# MCU.net
KiCad netlist of a schematic drawn in Altium Designer
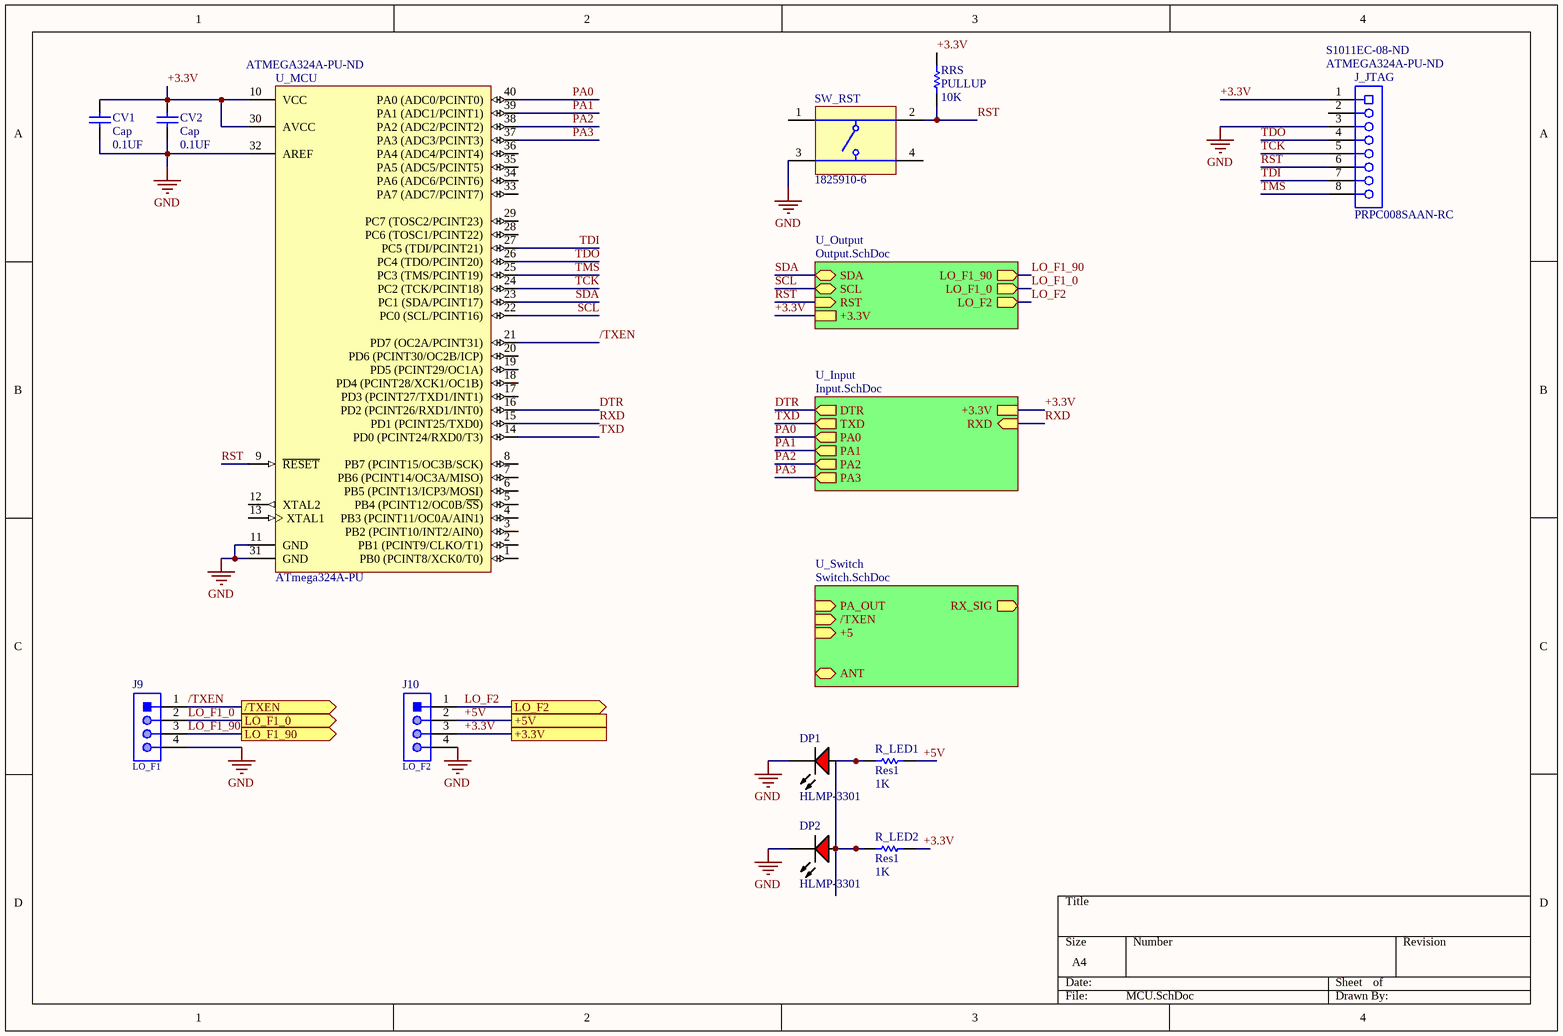
[diagram p0: MCU.SchDoc]

(export (version "E")
  (design (tool "Eeschema 10.0.6"))
  (components
    (comp (ref "CV1")
      (value "Cap")
      (footprint "1206")
      (description "Capacitor")
      (fields
        (field (name "ALTIUM_VALUE") "0.1UF")
        (field (name "MANUFACTURER PART NUMBER") "885012208087")
        (field (name "PUBLISHER") "Altium Limited")
      )
      (libsource (lib "ECE295-Capacitors-SMT") (part "CAP CER 0.1UF 50V X7R 1206"))
    )
    (comp (ref "CV2")
      (value "Cap")
      (footprint "1206")
      (description "Capacitor")
      (fields
        (field (name "ALTIUM_VALUE") "0.1UF")
        (field (name "MANUFACTURER PART NUMBER") "885012208087")
        (field (name "PUBLISHER") "Altium Limited")
      )
      (libsource (lib "ECE295-Capacitors-SMT") (part "CAP CER 0.1UF 50V X7R 1206"))
    )
    (comp (ref "DP1")
      (value "HLMP-3301")
      (footprint "AVAG-HLMP-3301-2")
      (description "T-1 3/4 (5 mm) Diffused LED Lamp, 1.9 V, -40 to 100 degC, 2-Pin THD, RoHS, Bulk")
      (fields (field (name "MANUFACTURER") "Avago"))
      (libsource (lib "Altium Content Vault") (part "LED-RED-K1A2-2"))
    )
    (comp (ref "DP2")
      (value "HLMP-3301")
      (footprint "AVAG-HLMP-3301-2")
      (description "T-1 3/4 (5 mm) Diffused LED Lamp, 1.9 V, -40 to 100 degC, 2-Pin THD, RoHS, Bulk")
      (fields (field (name "MANUFACTURER") "Avago"))
      (libsource (lib "Altium Content Vault") (part "LED-RED-K1A2-2"))
    )
    (comp (ref "J9")
      (value "LO_F1")
      (footprint "61300411121")
      (description "THT Vertical Pin Header WR-PHD, Pitch 2.54 mm, Single Row, 4 pins")
      (fields
        (field (name "MANUFACTURER") "Wurth Elektronik")
        (field (name "PART NUMBER") "61300411121")
        (field (name "PUBLISHER") "WurthElektronik")
      )
      (libsource (lib "Altium Content Vault") (part "WE-CN-1P-M-R4"))
    )
    (comp (ref "J10")
      (value "LO_F2")
      (footprint "61300411121")
      (description "THT Vertical Pin Header WR-PHD, Pitch 2.54 mm, Single Row, 4 pins")
      (fields
        (field (name "MANUFACTURER") "Wurth Elektronik")
        (field (name "PART NUMBER") "61300411121")
        (field (name "PUBLISHER") "WurthElektronik")
      )
      (libsource (lib "Altium Content Vault") (part "WE-CN-1P-M-R4"))
    )
    (comp (ref "J_JTAG")
      (value "PRPC008SAAN-RC")
      (footprint "SLIN-PPPC081LFBN-RC_V")
      (fields
        (field (name "SUPPLIER PART NUMBER 1") "ATMEGA324A-PU-ND")
        (field (name "MANUFACTURER") "Microchip")
        (field (name "MANUFACTURER PART NUMBER") "ATMEGA324A-PU")
        (field (name "SUPPLIER PART NUMBER 2") "S1011EC-08-ND")
      )
      (libsource (lib "Altium Content Vault") (part "CN-1P-F-R8"))
    )
    (comp (ref "RRS")
      (value "PULLUP")
      (footprint "AXIAL-0.1-RES")
      (description "Resistor")
      (fields
        (field (name "ALTIUM_VALUE") "10K")
        (field (name "MANUFACTURER PART NUMBER") "CFR-25JB-52-10K")
        (field (name "TOLERANCE") "0.05")
        (field (name "PUBLISHER") "Altium Limited")
      )
      (libsource (lib "ECE295-Resistors-TH") (part "RES 10K OHM 5% 1/4W AXIAL"))
    )
    (comp (ref "R_LED1")
      (value "Res1")
      (footprint "AXIAL-0.1-RES")
      (description "Resistor")
      (fields
        (field (name "MANUFACTURER PART NUMBER") "CFR-25JB-52-1K")
        (field (name "TOLERANCE") "0.05")
        (field (name "ALTIUM_VALUE") "1K")
        (field (name "PUBLISHER") "Altium Limited")
      )
      (libsource (lib "ECE295-Resistors-TH") (part "RES 1K OHM 5% 1/4W AXIAL"))
    )
    (comp (ref "R_LED2")
      (value "Res1")
      (footprint "AXIAL-0.1-RES")
      (description "Resistor")
      (fields
        (field (name "MANUFACTURER PART NUMBER") "CFR-25JB-52-1K")
        (field (name "TOLERANCE") "0.05")
        (field (name "ALTIUM_VALUE") "1K")
        (field (name "PUBLISHER") "Altium Limited")
      )
      (libsource (lib "ECE295-Resistors-TH") (part "RES 1K OHM 5% 1/4W AXIAL"))
    )
    (comp (ref "SW_RST")
      (value "1825910-6")
      (footprint "TECO-1825910-6_V")
      (description "Tact Switch, SPST-NO, 0.05 A, -35 to 85 degC, 4-Pin THD, RoHS, Bulk")
      (fields (field (name "MANUFACTURER") "TE Connectivity"))
      (libsource (lib "Altium Content Vault") (part "SW-SPST-4_A"))
    )
    (comp (ref "U_MCU")
      (value "ATmega324A-PU")
      (footprint "40P6")
      (fields
        (field (name "SUPPLIER PART NUMBER 1") "ATMEGA324A-PU-ND")
        (field (name "MANUFACTURER") "Microchip")
        (field (name "MANUFACTURER PART NUMBER") "ATMEGA324A-PU")
      )
      (libsource (lib "Altium Content Vault") (part "MC-8B-ATM128-IL40"))
    )
  )
  (nets
    (net (code "1") (name "/+3.3V") (class "Default")
      (node (ref "CV1") (pin "2") (pinfunction "2_2") (pintype "passive"))
      (node (ref "CV2") (pin "2") (pinfunction "2_2") (pintype "passive"))
      (node (ref "J10") (pin "3") (pinfunction "3_3") (pintype "passive"))
      (node (ref "J_JTAG") (pin "1") (pinfunction "1_1") (pintype "passive"))
      (node (ref "RRS") (pin "2") (pinfunction "2_2") (pintype "passive"))
      (node (ref "R_LED2") (pin "2") (pinfunction "2_2") (pintype "passive"))
      (node (ref "U_MCU") (pin "10") (pinfunction "VCC_10") (pintype "power_in"))
      (node (ref "U_MCU") (pin "30") (pinfunction "AVCC_30") (pintype "power_in"))
    )
    (net (code "3") (name "/+5V") (class "Default")
      (node (ref "J10") (pin "2") (pinfunction "2_2") (pintype "passive"))
      (node (ref "R_LED1") (pin "2") (pinfunction "2_2") (pintype "passive"))
    )
    (net (code "5") (name "/DTR") (class "Default")
      (node (ref "U_MCU") (pin "16") (pinfunction "PD2_(PCINT26/RXD1/INT0)_16") (pintype "bidirectional"))
    )
    (net (code "6") (name "/LO_F1_0") (class "Default")
      (node (ref "J9") (pin "2") (pinfunction "2_2") (pintype "passive"))
    )
    (net (code "7") (name "/LO_F1_90") (class "Default")
      (node (ref "J9") (pin "3") (pinfunction "3_3") (pintype "passive"))
    )
    (net (code "8") (name "/LO_F2") (class "Default")
      (node (ref "J10") (pin "1") (pinfunction "1_1") (pintype "passive"))
    )
    (net (code "9") (name "/PA0") (class "Default")
      (node (ref "U_MCU") (pin "40") (pinfunction "PA0_(ADC0/PCINT0)_40") (pintype "bidirectional"))
    )
    (net (code "10") (name "/PA1") (class "Default")
      (node (ref "U_MCU") (pin "39") (pinfunction "PA1_(ADC1/PCINT1)_39") (pintype "bidirectional"))
    )
    (net (code "11") (name "/PA2") (class "Default")
      (node (ref "U_MCU") (pin "38") (pinfunction "PA2_(ADC2/PCINT2)_38") (pintype "bidirectional"))
    )
    (net (code "12") (name "/PA3") (class "Default")
      (node (ref "U_MCU") (pin "37") (pinfunction "PA3_(ADC3/PCINT3)_37") (pintype "bidirectional"))
    )
    (net (code "14") (name "/RST") (class "Default")
      (node (ref "J_JTAG") (pin "6") (pinfunction "6_6") (pintype "passive"))
      (node (ref "RRS") (pin "1") (pinfunction "1_1") (pintype "passive"))
      (node (ref "SW_RST") (pin "2") (pinfunction "2_2") (pintype "passive"))
      (node (ref "U_MCU") (pin "9") (pinfunction "~{RESET}_9") (pintype "input"))
    )
    (net (code "15") (name "/RXD") (class "Default")
      (node (ref "U_MCU") (pin "15") (pinfunction "PD1_(PCINT25/TXD0)_15") (pintype "bidirectional"))
    )
    (net (code "17") (name "/SCL") (class "Default")
      (node (ref "U_MCU") (pin "22") (pinfunction "PC0_(SCL/PCINT16)_22") (pintype "bidirectional"))
    )
    (net (code "18") (name "/SDA") (class "Default")
      (node (ref "U_MCU") (pin "23") (pinfunction "PC1_(SDA/PCINT17)_23") (pintype "bidirectional"))
    )
    (net (code "19") (name "/TCK") (class "Default")
      (node (ref "J_JTAG") (pin "5") (pinfunction "5_5") (pintype "passive"))
      (node (ref "U_MCU") (pin "24") (pinfunction "PC2_(TCK/PCINT18)_24") (pintype "bidirectional"))
    )
    (net (code "20") (name "/TDI") (class "Default")
      (node (ref "J_JTAG") (pin "7") (pinfunction "7_7") (pintype "passive"))
      (node (ref "U_MCU") (pin "27") (pinfunction "PC5_(TDI/PCINT21)_27") (pintype "bidirectional"))
    )
    (net (code "21") (name "/TDO") (class "Default")
      (node (ref "J_JTAG") (pin "4") (pinfunction "4_4") (pintype "passive"))
      (node (ref "U_MCU") (pin "26") (pinfunction "PC4_(TDO/PCINT20)_26") (pintype "bidirectional"))
    )
    (net (code "22") (name "/TMS") (class "Default")
      (node (ref "J_JTAG") (pin "8") (pinfunction "8_8") (pintype "passive"))
      (node (ref "U_MCU") (pin "25") (pinfunction "PC3_(TMS/PCINT19)_25") (pintype "bidirectional"))
    )
    (net (code "23") (name "/TXD") (class "Default")
      (node (ref "U_MCU") (pin "14") (pinfunction "PD0_(PCINT24/RXD0/T3)_14") (pintype "bidirectional"))
    )
    (net (code "24") (name "/{slash}TXEN") (class "Default")
      (node (ref "J9") (pin "1") (pinfunction "1_1") (pintype "passive"))
      (node (ref "U_MCU") (pin "21") (pinfunction "PD7_(OC2A/PCINT31)_21") (pintype "bidirectional"))
    )
    (net (code "26") (name "GND") (class "Default")
      (node (ref "CV1") (pin "1") (pinfunction "1_1") (pintype "passive"))
      (node (ref "CV2") (pin "1") (pinfunction "1_1") (pintype "passive"))
      (node (ref "DP1") (pin "1") (pinfunction "K_1") (pintype "passive"))
      (node (ref "DP2") (pin "1") (pinfunction "K_1") (pintype "passive"))
      (node (ref "J10") (pin "4") (pinfunction "4_4") (pintype "passive"))
      (node (ref "J9") (pin "4") (pinfunction "4_4") (pintype "passive"))
      (node (ref "J_JTAG") (pin "3") (pinfunction "3_3") (pintype "passive"))
      (node (ref "SW_RST") (pin "3") (pinfunction "3_3") (pintype "passive"))
      (node (ref "U_MCU") (pin "11") (pinfunction "GND_11") (pintype "power_in"))
      (node (ref "U_MCU") (pin "31") (pinfunction "GND_31") (pintype "power_in"))
      (node (ref "U_MCU") (pin "32") (pinfunction "AREF_32") (pintype "power_in"))
    )
    (net (code "27") (name "Net-(DP1-A)") (class "Default")
      (node (ref "DP1") (pin "2") (pinfunction "A_2") (pintype "passive"))
      (node (ref "DP2") (pin "2") (pinfunction "A_2") (pintype "passive"))
      (node (ref "R_LED1") (pin "1") (pinfunction "1_1") (pintype "passive"))
      (node (ref "R_LED2") (pin "1") (pinfunction "1_1") (pintype "passive"))
    )
    (net (code "28") (name "unconnected-(J_JTAG-Pad2)") (class "Default")
      (node (ref "J_JTAG") (pin "2") (pinfunction "2_2") (pintype "passive"))
    )
    (net (code "29") (name "unconnected-(SW_RST-Pad1)") (class "Default")
      (node (ref "SW_RST") (pin "1") (pinfunction "1_1") (pintype "passive"))
    )
    (net (code "30") (name "unconnected-(SW_RST-Pad4)") (class "Default")
      (node (ref "SW_RST") (pin "4") (pinfunction "4_4") (pintype "passive"))
    )
    (net (code "31") (name "unconnected-(U_MCU-PA4_(ADC4{slash}PCINT4)-Pad36)") (class "Default")
      (node (ref "U_MCU") (pin "36") (pinfunction "PA4_(ADC4/PCINT4)_36") (pintype "bidirectional"))
    )
    (net (code "32") (name "unconnected-(U_MCU-PA5_(ADC5{slash}PCINT5)-Pad35)") (class "Default")
      (node (ref "U_MCU") (pin "35") (pinfunction "PA5_(ADC5/PCINT5)_35") (pintype "bidirectional"))
    )
    (net (code "33") (name "unconnected-(U_MCU-PA6_(ADC6{slash}PCINT6)-Pad34)") (class "Default")
      (node (ref "U_MCU") (pin "34") (pinfunction "PA6_(ADC6/PCINT6)_34") (pintype "bidirectional"))
    )
    (net (code "34") (name "unconnected-(U_MCU-PA7_(ADC7{slash}PCINT7)-Pad33)") (class "Default")
      (node (ref "U_MCU") (pin "33") (pinfunction "PA7_(ADC7/PCINT7)_33") (pintype "bidirectional"))
    )
    (net (code "35") (name "unconnected-(U_MCU-PB0_(PCINT8{slash}XCK0{slash}T0)-Pad1)") (class "Default")
      (node (ref "U_MCU") (pin "1") (pinfunction "PB0_(PCINT8/XCK0/T0)_1") (pintype "bidirectional"))
    )
    (net (code "36") (name "unconnected-(U_MCU-PB1_(PCINT9{slash}CLKO{slash}T1)-Pad2)") (class "Default")
      (node (ref "U_MCU") (pin "2") (pinfunction "PB1_(PCINT9/CLKO/T1)_2") (pintype "bidirectional"))
    )
    (net (code "37") (name "unconnected-(U_MCU-PB2_(PCINT10{slash}INT2{slash}AIN0)-Pad3)") (class "Default")
      (node (ref "U_MCU") (pin "3") (pinfunction "PB2_(PCINT10/INT2/AIN0)_3") (pintype "bidirectional"))
    )
    (net (code "38") (name "unconnected-(U_MCU-PB3_(PCINT11{slash}OC0A{slash}AIN1)-Pad4)") (class "Default")
      (node (ref "U_MCU") (pin "4") (pinfunction "PB3_(PCINT11/OC0A/AIN1)_4") (pintype "bidirectional"))
    )
    (net (code "39") (name "unconnected-(U_MCU-PB4_(PCINT12{slash}OC0B{slash}~{SS})-Pad5)") (class "Default")
      (node (ref "U_MCU") (pin "5") (pinfunction "PB4_(PCINT12/OC0B/~{SS})_5") (pintype "bidirectional"))
    )
    (net (code "40") (name "unconnected-(U_MCU-PB5_(PCINT13{slash}ICP3{slash}MOSI)-Pad6)") (class "Default")
      (node (ref "U_MCU") (pin "6") (pinfunction "PB5_(PCINT13/ICP3/MOSI)_6") (pintype "bidirectional"))
    )
    (net (code "41") (name "unconnected-(U_MCU-PB6_(PCINT14{slash}OC3A{slash}MISO)-Pad7)") (class "Default")
      (node (ref "U_MCU") (pin "7") (pinfunction "PB6_(PCINT14/OC3A/MISO)_7") (pintype "bidirectional"))
    )
    (net (code "42") (name "unconnected-(U_MCU-PB7_(PCINT15{slash}OC3B{slash}SCK)-Pad8)") (class "Default")
      (node (ref "U_MCU") (pin "8") (pinfunction "PB7_(PCINT15/OC3B/SCK)_8") (pintype "bidirectional"))
    )
    (net (code "43") (name "unconnected-(U_MCU-PC6_(TOSC1{slash}PCINT22)-Pad28)") (class "Default")
      (node (ref "U_MCU") (pin "28") (pinfunction "PC6_(TOSC1/PCINT22)_28") (pintype "bidirectional"))
    )
    (net (code "44") (name "unconnected-(U_MCU-PC7_(TOSC2{slash}PCINT23)-Pad29)") (class "Default")
      (node (ref "U_MCU") (pin "29") (pinfunction "PC7_(TOSC2/PCINT23)_29") (pintype "bidirectional"))
    )
    (net (code "45") (name "unconnected-(U_MCU-PD3_(PCINT27{slash}TXD1{slash}INT1)-Pad17)") (class "Default")
      (node (ref "U_MCU") (pin "17") (pinfunction "PD3_(PCINT27/TXD1/INT1)_17") (pintype "bidirectional"))
    )
    (net (code "46") (name "unconnected-(U_MCU-PD4_(PCINT28{slash}XCK1{slash}OC1B)-Pad18)") (class "Default")
      (node (ref "U_MCU") (pin "18") (pinfunction "PD4_(PCINT28/XCK1/OC1B)_18") (pintype "bidirectional"))
    )
    (net (code "47") (name "unconnected-(U_MCU-PD5_(PCINT29{slash}OC1A)-Pad19)") (class "Default")
      (node (ref "U_MCU") (pin "19") (pinfunction "PD5_(PCINT29/OC1A)_19") (pintype "bidirectional"))
    )
    (net (code "48") (name "unconnected-(U_MCU-PD6_(PCINT30{slash}OC2B{slash}ICP)-Pad20)") (class "Default")
      (node (ref "U_MCU") (pin "20") (pinfunction "PD6_(PCINT30/OC2B/ICP)_20") (pintype "bidirectional"))
    )
    (net (code "49") (name "unconnected-(U_MCU-XTAL1-Pad13)") (class "Default")
      (node (ref "U_MCU") (pin "13") (pinfunction "XTAL1_13") (pintype "input"))
    )
    (net (code "50") (name "unconnected-(U_MCU-XTAL2-Pad12)") (class "Default")
      (node (ref "U_MCU") (pin "12") (pinfunction "XTAL2_12") (pintype "output"))
    )
  )
)
